# n64cart-v3-soic-16.net
KiCad netlist of a schematic drawn in EAGLE
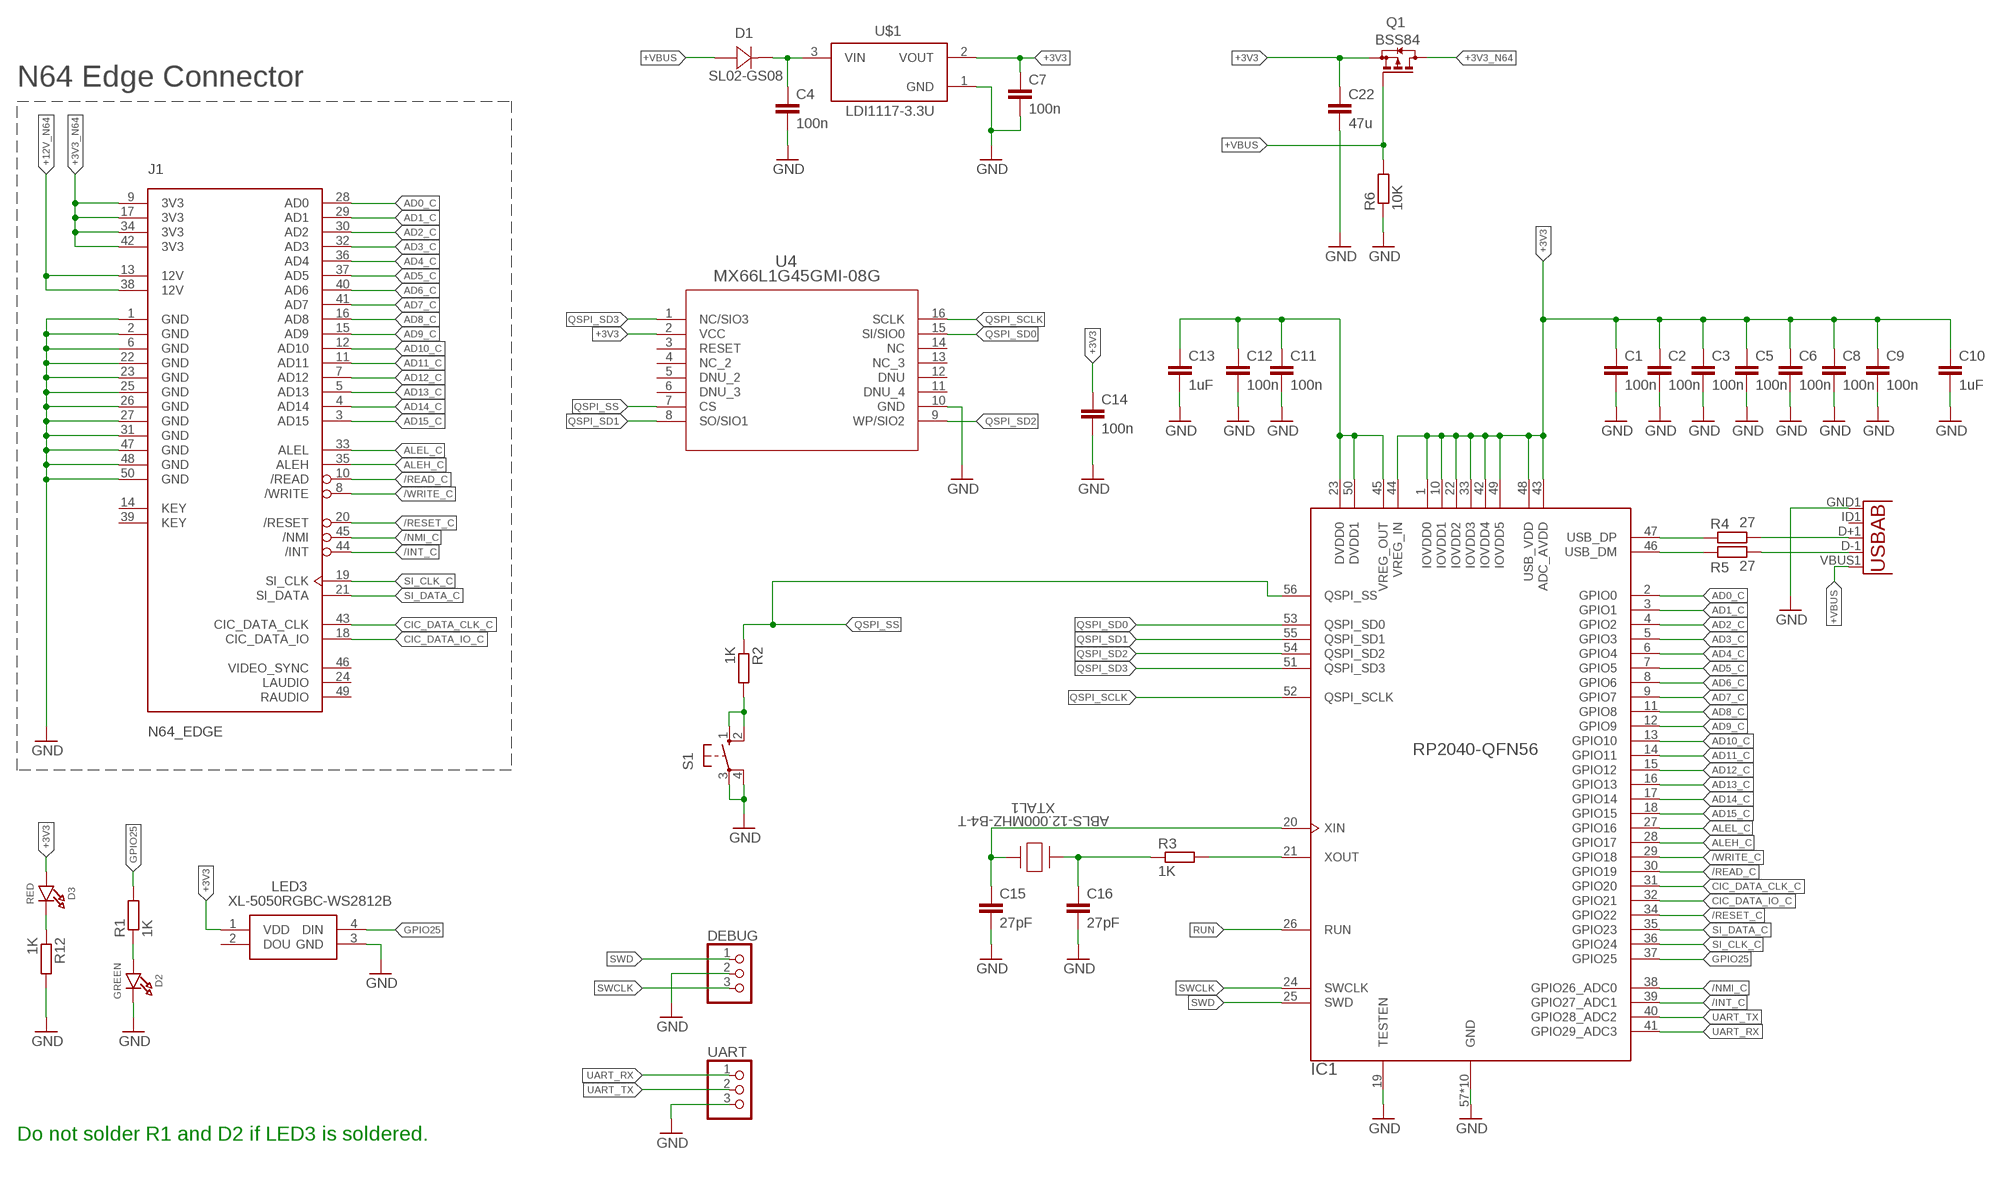
[diagram p0: schematic, sheet 1]

(export (version "E")
  (design (tool "Eeschema 10.0.6"))
  (components
    (comp (ref "C1")
      (value "100n")
      (footprint "eagle-import:C0402")
      (libsource (lib "eagle-import") (part "C-EUC0402"))
    )
    (comp (ref "C2")
      (value "100n")
      (footprint "eagle-import:C0402")
      (libsource (lib "eagle-import") (part "C-EUC0402"))
    )
    (comp (ref "C3")
      (value "100n")
      (footprint "eagle-import:C0402")
      (libsource (lib "eagle-import") (part "C-EUC0402"))
    )
    (comp (ref "C4")
      (value "100n")
      (footprint "eagle-import:C0603")
      (libsource (lib "eagle-import") (part "C-EUC0603"))
    )
    (comp (ref "C5")
      (value "100n")
      (footprint "eagle-import:C0402")
      (libsource (lib "eagle-import") (part "C-EUC0402"))
    )
    (comp (ref "C6")
      (value "100n")
      (footprint "eagle-import:C0402")
      (libsource (lib "eagle-import") (part "C-EUC0402"))
    )
    (comp (ref "C7")
      (value "100n")
      (footprint "eagle-import:C0603")
      (libsource (lib "eagle-import") (part "C-EUC0603"))
    )
    (comp (ref "C8")
      (value "100n")
      (footprint "eagle-import:C0402")
      (libsource (lib "eagle-import") (part "C-EUC0402"))
    )
    (comp (ref "C9")
      (value "100n")
      (footprint "eagle-import:C0402")
      (libsource (lib "eagle-import") (part "C-EUC0402"))
    )
    (comp (ref "C10")
      (value "1uF")
      (footprint "eagle-import:C0402")
      (libsource (lib "eagle-import") (part "C-EUC0402"))
    )
    (comp (ref "C11")
      (value "100n")
      (footprint "eagle-import:C0402")
      (libsource (lib "eagle-import") (part "C-EUC0402"))
    )
    (comp (ref "C12")
      (value "100n")
      (footprint "eagle-import:C0402")
      (libsource (lib "eagle-import") (part "C-EUC0402"))
    )
    (comp (ref "C13")
      (value "1uF")
      (footprint "eagle-import:C0402")
      (libsource (lib "eagle-import") (part "C-EUC0402"))
    )
    (comp (ref "C14")
      (value "100n")
      (footprint "eagle-import:C0402")
      (libsource (lib "eagle-import") (part "C-EUC0402"))
    )
    (comp (ref "C15")
      (value "27pF")
      (footprint "eagle-import:C0402")
      (libsource (lib "eagle-import") (part "C-EUC0402"))
    )
    (comp (ref "C16")
      (value "27pF")
      (footprint "eagle-import:C0402")
      (libsource (lib "eagle-import") (part "C-EUC0402"))
    )
    (comp (ref "C22")
      (value "47u")
      (footprint "eagle-import:C0805")
      (libsource (lib "eagle-import") (part "C-EUC0805"))
    )
    (comp (ref "D1")
      (value "SL02-GS08")
      (footprint "eagle-import:DIODE_SL02-GS08_VIS-M")
      (fields (field (name "COPYRIGHT") "Copyright (C) 2022 Ultra Librarian. All rights reserved."))
      (libsource (lib "eagle-import") (part "SL02-GS08DIODE_SL02-GS08_VIS-M"))
    )
    (comp (ref "D2")
      (value "GREEN")
      (footprint "eagle-import:CHIPLED_0603_NOOUTLINE")
      (libsource (lib "eagle-import") (part "LED0603_NOOUTLINE"))
    )
    (comp (ref "D3")
      (value "RED")
      (footprint "eagle-import:CHIPLED_0603_NOOUTLINE")
      (libsource (lib "eagle-import") (part "LED0603_NOOUTLINE"))
    )
    (comp (ref "DEBUG")
      (value "PINHD-1X3")
      (footprint "eagle-import:1X03")
      (libsource (lib "eagle-import") (part "PINHD-1X3"))
    )
    (comp (ref "IC1")
      (value "RP2040-QFN56")
      (footprint "eagle-import:RP2040-QFN-56")
      (libsource (lib "eagle-import") (part "RP2040-QFN56"))
    )
    (comp (ref "J1")
      (value "N64_EDGE")
      (footprint "eagle-import:N64_EDGE")
      (libsource (lib "eagle-import") (part "N64_EDGE"))
    )
    (comp (ref "LED3")
      (value "XL-5050RGBC-WS2812B")
      (footprint "eagle-import:XL5050RGBCWS2812B")
      (libsource (lib "eagle-import") (part "XL-5050RGBC-WS2812B"))
    )
    (comp (ref "Q1")
      (value "BSS84")
      (footprint "eagle-import:SOT23")
      (libsource (lib "eagle-import") (part "BSS84"))
    )
    (comp (ref "R1")
      (value "1K")
      (footprint "eagle-import:R0603")
      (libsource (lib "eagle-import") (part "R-EU_R0603"))
    )
    (comp (ref "R2")
      (value "1K")
      (footprint "eagle-import:R0402")
      (libsource (lib "eagle-import") (part "R-EU_R0402"))
    )
    (comp (ref "R3")
      (value "1K")
      (footprint "eagle-import:R0402")
      (libsource (lib "eagle-import") (part "R-EU_R0402"))
    )
    (comp (ref "R4")
      (value "27")
      (footprint "eagle-import:R0402")
      (libsource (lib "eagle-import") (part "R-EU_R0402"))
    )
    (comp (ref "R5")
      (value "27")
      (footprint "eagle-import:R0402")
      (libsource (lib "eagle-import") (part "R-EU_R0402"))
    )
    (comp (ref "R6")
      (value "10K")
      (footprint "eagle-import:R0603")
      (libsource (lib "eagle-import") (part "R-EU_R0603"))
    )
    (comp (ref "R12")
      (value "1K")
      (footprint "eagle-import:R0603")
      (libsource (lib "eagle-import") (part "R-EU_R0603"))
    )
    (comp (ref "S1")
      (value "10-XX")
      (footprint "eagle-import:B3F-10XX")
      (fields (field (name "MPN") "B3F-1000"))
      (libsource (lib "eagle-import") (part "10-XX"))
    )
    (comp (ref "U$1")
      (value "LDI1117-3.3U")
      (footprint "eagle-import:LDI1117-3.3U")
      (libsource (lib "eagle-import") (part "LDI1117-3.3U"))
    )
    (comp (ref "U2")
      (value "USB\"\"")
      (footprint "eagle-import:USB-MICRO-SMD")
      (libsource (lib "eagle-import") (part "USB{dblquote}{dblquote}"))
    )
    (comp (ref "U4")
      (value "MX66L1G45GMI-08G")
      (footprint "eagle-import:SOP_16L_300_MAC-L")
      (fields (field (name "COPYRIGHT") "Copyright (C) 2024 Ultra Librarian. All rights reserved."))
      (libsource (lib "eagle-import") (part "MX66L1G45GMI-08GSOP_16L_300_MAC-L"))
    )
    (comp (ref "UART")
      (value "PINHD-1X3")
      (footprint "eagle-import:1X03")
      (libsource (lib "eagle-import") (part "PINHD-1X3"))
    )
    (comp (ref "XTAL1")
      (value "ABLS-12.000MHZ-B4-T")
      (footprint "eagle-import:XTAL_ABLS_ABR")
      (fields (field (name "COPYRIGHT") "Copyright (C) 2022 Ultra Librarian. All rights reserved."))
      (libsource (lib "eagle-import") (part "ABLS-12.000MHZ-B4-T"))
    )
  )
  (nets
    (net (code "1") (name "+3V3") (class "Default")
      (node (ref "C1") (pin "1") (pinfunction "1_1") (pintype "passive"))
      (node (ref "C10") (pin "1") (pinfunction "1_1") (pintype "passive"))
      (node (ref "C14") (pin "1") (pinfunction "1_1") (pintype "passive"))
      (node (ref "C2") (pin "1") (pinfunction "1_1") (pintype "passive"))
      (node (ref "C22") (pin "1") (pinfunction "1_1") (pintype "passive"))
      (node (ref "C3") (pin "1") (pinfunction "1_1") (pintype "passive"))
      (node (ref "C5") (pin "1") (pinfunction "1_1") (pintype "passive"))
      (node (ref "C6") (pin "1") (pinfunction "1_1") (pintype "passive"))
      (node (ref "C7") (pin "1") (pinfunction "1_1") (pintype "passive"))
      (node (ref "C8") (pin "1") (pinfunction "1_1") (pintype "passive"))
      (node (ref "C9") (pin "1") (pinfunction "1_1") (pintype "passive"))
      (node (ref "D3") (pin "A") (pinfunction "A_A") (pintype "passive"))
      (node (ref "IC1") (pin "1") (pinfunction "IOVDD0_1") (pintype "power_in"))
      (node (ref "IC1") (pin "10") (pinfunction "IOVDD1_10") (pintype "power_in"))
      (node (ref "IC1") (pin "22") (pinfunction "IOVDD2_22") (pintype "power_in"))
      (node (ref "IC1") (pin "33") (pinfunction "IOVDD3_33") (pintype "power_in"))
      (node (ref "IC1") (pin "42") (pinfunction "IOVDD4_42") (pintype "power_in"))
      (node (ref "IC1") (pin "43") (pinfunction "ADC_AVDD_43") (pintype "power_in"))
      (node (ref "IC1") (pin "44") (pinfunction "VREG_IN_44") (pintype "power_in"))
      (node (ref "IC1") (pin "48") (pinfunction "USB_VDD_48") (pintype "power_in"))
      (node (ref "IC1") (pin "49") (pinfunction "IOVDD5_49") (pintype "power_in"))
      (node (ref "LED3") (pin "1") (pinfunction "VDD_1") (pintype "bidirectional"))
      (node (ref "Q1") (pin "2") (pinfunction "S_2") (pintype "passive"))
      (node (ref "U$1") (pin "2") (pinfunction "VOUT_2") (pintype "output"))
      (node (ref "U4") (pin "2") (pinfunction "VCC_2") (pintype "power_in"))
    )
    (net (code "2") (name "+3V3_N64") (class "Default")
      (node (ref "J1") (pin "17") (pinfunction "3V3_17") (pintype "power_in"))
      (node (ref "J1") (pin "34") (pinfunction "3V3_34") (pintype "power_in"))
      (node (ref "J1") (pin "42") (pinfunction "3V3_42") (pintype "power_in"))
      (node (ref "J1") (pin "9") (pinfunction "3V3_9") (pintype "power_in"))
      (node (ref "Q1") (pin "3") (pinfunction "D_3") (pintype "passive"))
    )
    (net (code "3") (name "+12V_N64") (class "Default")
      (node (ref "J1") (pin "13") (pinfunction "12V_13") (pintype "power_in"))
      (node (ref "J1") (pin "38") (pinfunction "12V_38") (pintype "power_in"))
    )
    (net (code "4") (name "+VBUS") (class "Default")
      (node (ref "D1") (pin "2") (pinfunction "2_2") (pintype "passive"))
      (node (ref "Q1") (pin "1") (pinfunction "G_1") (pintype "passive"))
      (node (ref "R6") (pin "2") (pinfunction "2_2") (pintype "passive"))
      (node (ref "U2") (pin "VBUS1") (pinfunction "VBUS_VBUS1") (pintype "bidirectional"))
    )
    (net (code "5") (name "AD0_C") (class "Default")
      (node (ref "IC1") (pin "2") (pinfunction "GPIO0_2") (pintype "bidirectional"))
      (node (ref "J1") (pin "28") (pinfunction "AD0_28") (pintype "bidirectional"))
    )
    (net (code "6") (name "AD1_C") (class "Default")
      (node (ref "IC1") (pin "3") (pinfunction "GPIO1_3") (pintype "bidirectional"))
      (node (ref "J1") (pin "29") (pinfunction "AD1_29") (pintype "bidirectional"))
    )
    (net (code "7") (name "AD2_C") (class "Default")
      (node (ref "IC1") (pin "4") (pinfunction "GPIO2_4") (pintype "bidirectional"))
      (node (ref "J1") (pin "30") (pinfunction "AD2_30") (pintype "bidirectional"))
    )
    (net (code "8") (name "AD3_C") (class "Default")
      (node (ref "IC1") (pin "5") (pinfunction "GPIO3_5") (pintype "bidirectional"))
      (node (ref "J1") (pin "32") (pinfunction "AD3_32") (pintype "bidirectional"))
    )
    (net (code "9") (name "AD4_C") (class "Default")
      (node (ref "IC1") (pin "6") (pinfunction "GPIO4_6") (pintype "bidirectional"))
      (node (ref "J1") (pin "36") (pinfunction "AD4_36") (pintype "bidirectional"))
    )
    (net (code "10") (name "AD5_C") (class "Default")
      (node (ref "IC1") (pin "7") (pinfunction "GPIO5_7") (pintype "bidirectional"))
      (node (ref "J1") (pin "37") (pinfunction "AD5_37") (pintype "bidirectional"))
    )
    (net (code "11") (name "AD6_C") (class "Default")
      (node (ref "IC1") (pin "8") (pinfunction "GPIO6_8") (pintype "bidirectional"))
      (node (ref "J1") (pin "40") (pinfunction "AD6_40") (pintype "bidirectional"))
    )
    (net (code "12") (name "AD7_C") (class "Default")
      (node (ref "IC1") (pin "9") (pinfunction "GPIO7_9") (pintype "bidirectional"))
      (node (ref "J1") (pin "41") (pinfunction "AD7_41") (pintype "bidirectional"))
    )
    (net (code "13") (name "AD8_C") (class "Default")
      (node (ref "IC1") (pin "11") (pinfunction "GPIO8_11") (pintype "bidirectional"))
      (node (ref "J1") (pin "16") (pinfunction "AD8_16") (pintype "bidirectional"))
    )
    (net (code "14") (name "AD9_C") (class "Default")
      (node (ref "IC1") (pin "12") (pinfunction "GPIO9_12") (pintype "bidirectional"))
      (node (ref "J1") (pin "15") (pinfunction "AD9_15") (pintype "bidirectional"))
    )
    (net (code "15") (name "AD10_C") (class "Default")
      (node (ref "IC1") (pin "13") (pinfunction "GPIO10_13") (pintype "bidirectional"))
      (node (ref "J1") (pin "12") (pinfunction "AD10_12") (pintype "bidirectional"))
    )
    (net (code "16") (name "AD11_C") (class "Default")
      (node (ref "IC1") (pin "14") (pinfunction "GPIO11_14") (pintype "bidirectional"))
      (node (ref "J1") (pin "11") (pinfunction "AD11_11") (pintype "bidirectional"))
    )
    (net (code "17") (name "AD12_C") (class "Default")
      (node (ref "IC1") (pin "15") (pinfunction "GPIO12_15") (pintype "bidirectional"))
      (node (ref "J1") (pin "7") (pinfunction "AD12_7") (pintype "bidirectional"))
    )
    (net (code "18") (name "AD13_C") (class "Default")
      (node (ref "IC1") (pin "16") (pinfunction "GPIO13_16") (pintype "bidirectional"))
      (node (ref "J1") (pin "5") (pinfunction "AD13_5") (pintype "bidirectional"))
    )
    (net (code "19") (name "AD14_C") (class "Default")
      (node (ref "IC1") (pin "17") (pinfunction "GPIO14_17") (pintype "bidirectional"))
      (node (ref "J1") (pin "4") (pinfunction "AD14_4") (pintype "bidirectional"))
    )
    (net (code "20") (name "AD15_C") (class "Default")
      (node (ref "IC1") (pin "18") (pinfunction "GPIO15_18") (pintype "bidirectional"))
      (node (ref "J1") (pin "3") (pinfunction "AD15_3") (pintype "bidirectional"))
    )
    (net (code "21") (name "ALEH_C") (class "Default")
      (node (ref "IC1") (pin "28") (pinfunction "GPIO17_28") (pintype "bidirectional"))
      (node (ref "J1") (pin "35") (pinfunction "ALEH_35") (pintype "output"))
    )
    (net (code "22") (name "ALEL_C") (class "Default")
      (node (ref "IC1") (pin "27") (pinfunction "GPIO16_27") (pintype "bidirectional"))
      (node (ref "J1") (pin "33") (pinfunction "ALEL_33") (pintype "output"))
    )
    (net (code "23") (name "CIC_DATA_CLK_C") (class "Default")
      (node (ref "IC1") (pin "31") (pinfunction "GPIO20_31") (pintype "bidirectional"))
      (node (ref "J1") (pin "43") (pinfunction "CIC_DATA_CLK_43") (pintype "output"))
    )
    (net (code "24") (name "CIC_DATA_IO_C") (class "Default")
      (node (ref "IC1") (pin "32") (pinfunction "GPIO21_32") (pintype "bidirectional"))
      (node (ref "J1") (pin "18") (pinfunction "CIC_DATA_IO_18") (pintype "bidirectional"))
    )
    (net (code "25") (name "GND") (class "Default")
      (node (ref "C1") (pin "2") (pinfunction "2_2") (pintype "passive"))
      (node (ref "C10") (pin "2") (pinfunction "2_2") (pintype "passive"))
      (node (ref "C11") (pin "2") (pinfunction "2_2") (pintype "passive"))
      (node (ref "C12") (pin "2") (pinfunction "2_2") (pintype "passive"))
      (node (ref "C13") (pin "2") (pinfunction "2_2") (pintype "passive"))
      (node (ref "C14") (pin "2") (pinfunction "2_2") (pintype "passive"))
      (node (ref "C15") (pin "2") (pinfunction "2_2") (pintype "passive"))
      (node (ref "C16") (pin "2") (pinfunction "2_2") (pintype "passive"))
      (node (ref "C2") (pin "2") (pinfunction "2_2") (pintype "passive"))
      (node (ref "C22") (pin "2") (pinfunction "2_2") (pintype "passive"))
      (node (ref "C3") (pin "2") (pinfunction "2_2") (pintype "passive"))
      (node (ref "C4") (pin "2") (pinfunction "2_2") (pintype "passive"))
      (node (ref "C5") (pin "2") (pinfunction "2_2") (pintype "passive"))
      (node (ref "C6") (pin "2") (pinfunction "2_2") (pintype "passive"))
      (node (ref "C7") (pin "2") (pinfunction "2_2") (pintype "passive"))
      (node (ref "C8") (pin "2") (pinfunction "2_2") (pintype "passive"))
      (node (ref "C9") (pin "2") (pinfunction "2_2") (pintype "passive"))
      (node (ref "D2") (pin "C") (pinfunction "C_C") (pintype "passive"))
      (node (ref "DEBUG") (pin "2") (pinfunction "2_2") (pintype "passive"))
      (node (ref "IC1") (pin "19") (pinfunction "TESTEN_19") (pintype "passive"))
      (node (ref "IC1") (pin "57") (pinfunction "GND_57") (pintype "power_in"))
      (node (ref "IC1") (pin "58") (pinfunction "GND_58") (pintype "power_in"))
      (node (ref "IC1") (pin "59") (pinfunction "GND_59") (pintype "power_in"))
      (node (ref "IC1") (pin "60") (pinfunction "GND_60") (pintype "power_in"))
      (node (ref "IC1") (pin "61") (pinfunction "GND_61") (pintype "power_in"))
      (node (ref "IC1") (pin "62") (pinfunction "GND_62") (pintype "power_in"))
      (node (ref "IC1") (pin "63") (pinfunction "GND_63") (pintype "power_in"))
      (node (ref "IC1") (pin "64") (pinfunction "GND_64") (pintype "power_in"))
      (node (ref "IC1") (pin "65") (pinfunction "GND_65") (pintype "power_in"))
      (node (ref "IC1") (pin "66") (pinfunction "GND_66") (pintype "power_in"))
      (node (ref "J1") (pin "1") (pinfunction "GND_1") (pintype "power_in"))
      (node (ref "J1") (pin "2") (pinfunction "GND_2") (pintype "power_in"))
      (node (ref "J1") (pin "22") (pinfunction "GND_22") (pintype "power_in"))
      (node (ref "J1") (pin "23") (pinfunction "GND_23") (pintype "power_in"))
      (node (ref "J1") (pin "25") (pinfunction "GND_25") (pintype "power_in"))
      (node (ref "J1") (pin "26") (pinfunction "GND_26") (pintype "power_in"))
      (node (ref "J1") (pin "27") (pinfunction "GND_27") (pintype "power_in"))
      (node (ref "J1") (pin "31") (pinfunction "GND_31") (pintype "power_in"))
      (node (ref "J1") (pin "47") (pinfunction "GND_47") (pintype "power_in"))
      (node (ref "J1") (pin "48") (pinfunction "GND_48") (pintype "power_in"))
      (node (ref "J1") (pin "50") (pinfunction "GND_50") (pintype "power_in"))
      (node (ref "J1") (pin "6") (pinfunction "GND_6") (pintype "power_in"))
      (node (ref "LED3") (pin "3") (pinfunction "GND_3") (pintype "bidirectional"))
      (node (ref "R12") (pin "2") (pinfunction "2_2") (pintype "passive"))
      (node (ref "R6") (pin "1") (pinfunction "1_1") (pintype "passive"))
      (node (ref "S1") (pin "3") (pinfunction "P_3") (pintype "passive"))
      (node (ref "S1") (pin "4") (pinfunction "P1_4") (pintype "passive"))
      (node (ref "U$1") (pin "1") (pinfunction "GND_1") (pintype "power_in"))
      (node (ref "U2") (pin "GND1") (pinfunction "GND_GND1") (pintype "bidirectional"))
      (node (ref "U4") (pin "10") (pinfunction "GND_10") (pintype "passive"))
      (node (ref "UART") (pin "3") (pinfunction "3_3") (pintype "passive"))
    )
    (net (code "26") (name "GPIO25") (class "Default")
      (node (ref "IC1") (pin "37") (pinfunction "GPIO25_37") (pintype "bidirectional"))
      (node (ref "LED3") (pin "4") (pinfunction "DIN_4") (pintype "bidirectional"))
      (node (ref "R1") (pin "2") (pinfunction "2_2") (pintype "passive"))
    )
    (net (code "27") (name "Net-(C16-Pad1)") (class "Default")
      (node (ref "C16") (pin "1") (pinfunction "1_1") (pintype "passive"))
      (node (ref "R3") (pin "1") (pinfunction "1_1") (pintype "passive"))
      (node (ref "XTAL1") (pin "1") (pinfunction "1_1") (pintype "passive"))
    )
    (net (code "28") (name "Net-(D2-PadA)") (class "Default")
      (node (ref "D2") (pin "A") (pinfunction "A_A") (pintype "passive"))
      (node (ref "R1") (pin "1") (pinfunction "1_1") (pintype "passive"))
    )
    (net (code "29") (name "Net-(D3-PadC)") (class "Default")
      (node (ref "D3") (pin "C") (pinfunction "C_C") (pintype "passive"))
      (node (ref "R12") (pin "1") (pinfunction "1_1") (pintype "passive"))
    )
    (net (code "30") (name "Net-(IC1-DVDD0)") (class "Default")
      (node (ref "C11") (pin "1") (pinfunction "1_1") (pintype "passive"))
      (node (ref "C12") (pin "1") (pinfunction "1_1") (pintype "passive"))
      (node (ref "C13") (pin "1") (pinfunction "1_1") (pintype "passive"))
      (node (ref "IC1") (pin "23") (pinfunction "DVDD0_23") (pintype "power_in"))
      (node (ref "IC1") (pin "45") (pinfunction "VREG_OUT_45") (pintype "power_in"))
      (node (ref "IC1") (pin "50") (pinfunction "DVDD1_50") (pintype "power_in"))
    )
    (net (code "31") (name "Net-(IC1-USB_DM)") (class "Default")
      (node (ref "IC1") (pin "46") (pinfunction "USB_DM_46") (pintype "bidirectional"))
      (node (ref "R5") (pin "1") (pinfunction "1_1") (pintype "passive"))
    )
    (net (code "32") (name "Net-(IC1-USB_DP)") (class "Default")
      (node (ref "IC1") (pin "47") (pinfunction "USB_DP_47") (pintype "bidirectional"))
      (node (ref "R4") (pin "1") (pinfunction "1_1") (pintype "passive"))
    )
    (net (code "33") (name "Net-(IC1-XIN)") (class "Default")
      (node (ref "C15") (pin "1") (pinfunction "1_1") (pintype "passive"))
      (node (ref "IC1") (pin "20") (pinfunction "XIN_20") (pintype "input"))
      (node (ref "XTAL1") (pin "2") (pinfunction "2_2") (pintype "passive"))
    )
    (net (code "34") (name "Net-(IC1-XOUT)") (class "Default")
      (node (ref "IC1") (pin "21") (pinfunction "XOUT_21") (pintype "passive"))
      (node (ref "R3") (pin "2") (pinfunction "2_2") (pintype "passive"))
    )
    (net (code "35") (name "Net-(S1-S)") (class "Default")
      (node (ref "R2") (pin "2") (pinfunction "2_2") (pintype "passive"))
      (node (ref "S1") (pin "1") (pinfunction "S_1") (pintype "passive"))
      (node (ref "S1") (pin "2") (pinfunction "S1_2") (pintype "passive"))
    )
    (net (code "36") (name "Net-(U$1-VIN)") (class "Default")
      (node (ref "C4") (pin "1") (pinfunction "1_1") (pintype "passive"))
      (node (ref "D1") (pin "1") (pinfunction "1_1") (pintype "passive"))
      (node (ref "U$1") (pin "3") (pinfunction "VIN_3") (pintype "input"))
    )
    (net (code "37") (name "Net-(U2-D+)") (class "Default")
      (node (ref "R4") (pin "2") (pinfunction "2_2") (pintype "passive"))
      (node (ref "U2") (pin "D+1") (pinfunction "D+_D+1") (pintype "bidirectional"))
    )
    (net (code "38") (name "Net-(U2-D-)") (class "Default")
      (node (ref "R5") (pin "2") (pinfunction "2_2") (pintype "passive"))
      (node (ref "U2") (pin "D-1") (pinfunction "D-_D-1") (pintype "bidirectional"))
    )
    (net (code "39") (name "QSPI_SCLK") (class "Default")
      (node (ref "IC1") (pin "52") (pinfunction "QSPI_SCLK_52") (pintype "output"))
      (node (ref "U4") (pin "16") (pinfunction "SCLK_16") (pintype "input"))
    )
    (net (code "40") (name "QSPI_SD0") (class "Default")
      (node (ref "IC1") (pin "53") (pinfunction "QSPI_SD0_53") (pintype "bidirectional"))
      (node (ref "U4") (pin "15") (pinfunction "SI/SIO0_15") (pintype "bidirectional"))
    )
    (net (code "41") (name "QSPI_SD1") (class "Default")
      (node (ref "IC1") (pin "55") (pinfunction "QSPI_SD1_55") (pintype "bidirectional"))
      (node (ref "U4") (pin "8") (pinfunction "SO/SIO1_8") (pintype "bidirectional"))
    )
    (net (code "42") (name "QSPI_SD2") (class "Default")
      (node (ref "IC1") (pin "54") (pinfunction "QSPI_SD2_54") (pintype "bidirectional"))
      (node (ref "U4") (pin "9") (pinfunction "WP/SIO2_9") (pintype "bidirectional"))
    )
    (net (code "43") (name "QSPI_SD3") (class "Default")
      (node (ref "IC1") (pin "51") (pinfunction "QSPI_SD3_51") (pintype "bidirectional"))
      (node (ref "U4") (pin "1") (pinfunction "NC/SIO3_1") (pintype "passive"))
    )
    (net (code "44") (name "QSPI_SS") (class "Default")
      (node (ref "IC1") (pin "56") (pinfunction "QSPI_SS_56") (pintype "bidirectional"))
      (node (ref "R2") (pin "1") (pinfunction "1_1") (pintype "passive"))
      (node (ref "U4") (pin "7") (pinfunction "CS_7") (pintype "input"))
    )
    (net (code "45") (name "RUN") (class "Default")
      (node (ref "IC1") (pin "26") (pinfunction "RUN_26") (pintype "input"))
    )
    (net (code "46") (name "SI_CLK_C") (class "Default")
      (node (ref "IC1") (pin "36") (pinfunction "GPIO24_36") (pintype "bidirectional"))
      (node (ref "J1") (pin "19") (pinfunction "SI_CLK_19") (pintype "output"))
    )
    (net (code "47") (name "SI_DATA_C") (class "Default")
      (node (ref "IC1") (pin "35") (pinfunction "GPIO23_35") (pintype "bidirectional"))
      (node (ref "J1") (pin "21") (pinfunction "SI_DATA_21") (pintype "bidirectional"))
    )
    (net (code "48") (name "SWCLK") (class "Default")
      (node (ref "DEBUG") (pin "3") (pinfunction "3_3") (pintype "passive"))
      (node (ref "IC1") (pin "24") (pinfunction "SWCLK_24") (pintype "output"))
    )
    (net (code "49") (name "SWD") (class "Default")
      (node (ref "DEBUG") (pin "1") (pinfunction "1_1") (pintype "passive"))
      (node (ref "IC1") (pin "25") (pinfunction "SWD_25") (pintype "bidirectional"))
    )
    (net (code "50") (name "UART_RX") (class "Default")
      (node (ref "IC1") (pin "41") (pinfunction "GPIO29_ADC3_41") (pintype "bidirectional"))
      (node (ref "UART") (pin "1") (pinfunction "1_1") (pintype "passive"))
    )
    (net (code "51") (name "UART_TX") (class "Default")
      (node (ref "IC1") (pin "40") (pinfunction "GPIO28_ADC2_40") (pintype "bidirectional"))
      (node (ref "UART") (pin "2") (pinfunction "2_2") (pintype "passive"))
    )
    (net (code "52") (name "unconnected-(J1-KEY-Pad14)") (class "Default")
      (node (ref "J1") (pin "14") (pinfunction "KEY_14") (pintype "no_connect"))
    )
    (net (code "53") (name "unconnected-(J1-KEY-Pad39)") (class "Default")
      (node (ref "J1") (pin "39") (pinfunction "KEY_39") (pintype "no_connect"))
    )
    (net (code "54") (name "unconnected-(J1-LAUDIO-Pad24)") (class "Default")
      (node (ref "J1") (pin "24") (pinfunction "LAUDIO_24") (pintype "input"))
    )
    (net (code "55") (name "unconnected-(J1-RAUDIO-Pad49)") (class "Default")
      (node (ref "J1") (pin "49") (pinfunction "RAUDIO_49") (pintype "input"))
    )
    (net (code "56") (name "unconnected-(J1-VIDEO_SYNC-Pad46)") (class "Default")
      (node (ref "J1") (pin "46") (pinfunction "VIDEO_SYNC_46") (pintype "output"))
    )
    (net (code "57") (name "unconnected-(LED3-DOU-Pad2)") (class "Default")
      (node (ref "LED3") (pin "2") (pinfunction "DOU_2") (pintype "bidirectional"))
    )
    (net (code "58") (name "unconnected-(U2-USBID-PadID1)") (class "Default")
      (node (ref "U2") (pin "ID1") (pinfunction "USBID_ID1") (pintype "bidirectional"))
    )
    (net (code "59") (name "unconnected-(U4-DNU-Pad12)") (class "Default")
      (node (ref "U4") (pin "12") (pinfunction "DNU_12") (pintype "no_connect"))
    )
    (net (code "60") (name "unconnected-(U4-DNU_2-Pad5)") (class "Default")
      (node (ref "U4") (pin "5") (pinfunction "DNU_2_5") (pintype "no_connect"))
    )
    (net (code "61") (name "unconnected-(U4-DNU_3-Pad6)") (class "Default")
      (node (ref "U4") (pin "6") (pinfunction "DNU_3_6") (pintype "no_connect"))
    )
    (net (code "62") (name "unconnected-(U4-DNU_4-Pad11)") (class "Default")
      (node (ref "U4") (pin "11") (pinfunction "DNU_4_11") (pintype "no_connect"))
    )
    (net (code "63") (name "unconnected-(U4-NC-Pad14)") (class "Default")
      (node (ref "U4") (pin "14") (pinfunction "NC_14") (pintype "no_connect"))
    )
    (net (code "64") (name "unconnected-(U4-NC_2-Pad4)") (class "Default")
      (node (ref "U4") (pin "4") (pinfunction "NC_2_4") (pintype "no_connect"))
    )
    (net (code "65") (name "unconnected-(U4-NC_3-Pad13)") (class "Default")
      (node (ref "U4") (pin "13") (pinfunction "NC_3_13") (pintype "no_connect"))
    )
    (net (code "66") (name "unconnected-(U4-RESET-Pad3)") (class "Default")
      (node (ref "U4") (pin "3") (pinfunction "RESET_3") (pintype "input"))
    )
    (net (code "67") (name "{slash}INT_C") (class "Default")
      (node (ref "IC1") (pin "39") (pinfunction "GPIO27_ADC1_39") (pintype "bidirectional"))
      (node (ref "J1") (pin "44") (pinfunction "/INT_44") (pintype "input"))
    )
    (net (code "68") (name "{slash}NMI_C") (class "Default")
      (node (ref "IC1") (pin "38") (pinfunction "GPIO26_ADC0_38") (pintype "bidirectional"))
      (node (ref "J1") (pin "45") (pinfunction "/NMI_45") (pintype "output"))
    )
    (net (code "69") (name "{slash}READ_C") (class "Default")
      (node (ref "IC1") (pin "30") (pinfunction "GPIO19_30") (pintype "bidirectional"))
      (node (ref "J1") (pin "10") (pinfunction "/READ_10") (pintype "output"))
    )
    (net (code "70") (name "{slash}RESET_C") (class "Default")
      (node (ref "IC1") (pin "34") (pinfunction "GPIO22_34") (pintype "bidirectional"))
      (node (ref "J1") (pin "20") (pinfunction "/RESET_20") (pintype "output"))
    )
    (net (code "71") (name "{slash}WRITE_C") (class "Default")
      (node (ref "IC1") (pin "29") (pinfunction "GPIO18_29") (pintype "bidirectional"))
      (node (ref "J1") (pin "8") (pinfunction "/WRITE_8") (pintype "output"))
    )
  )
)
